# fpga-power.net
KiCad netlist of a schematic drawn in Altium Designer
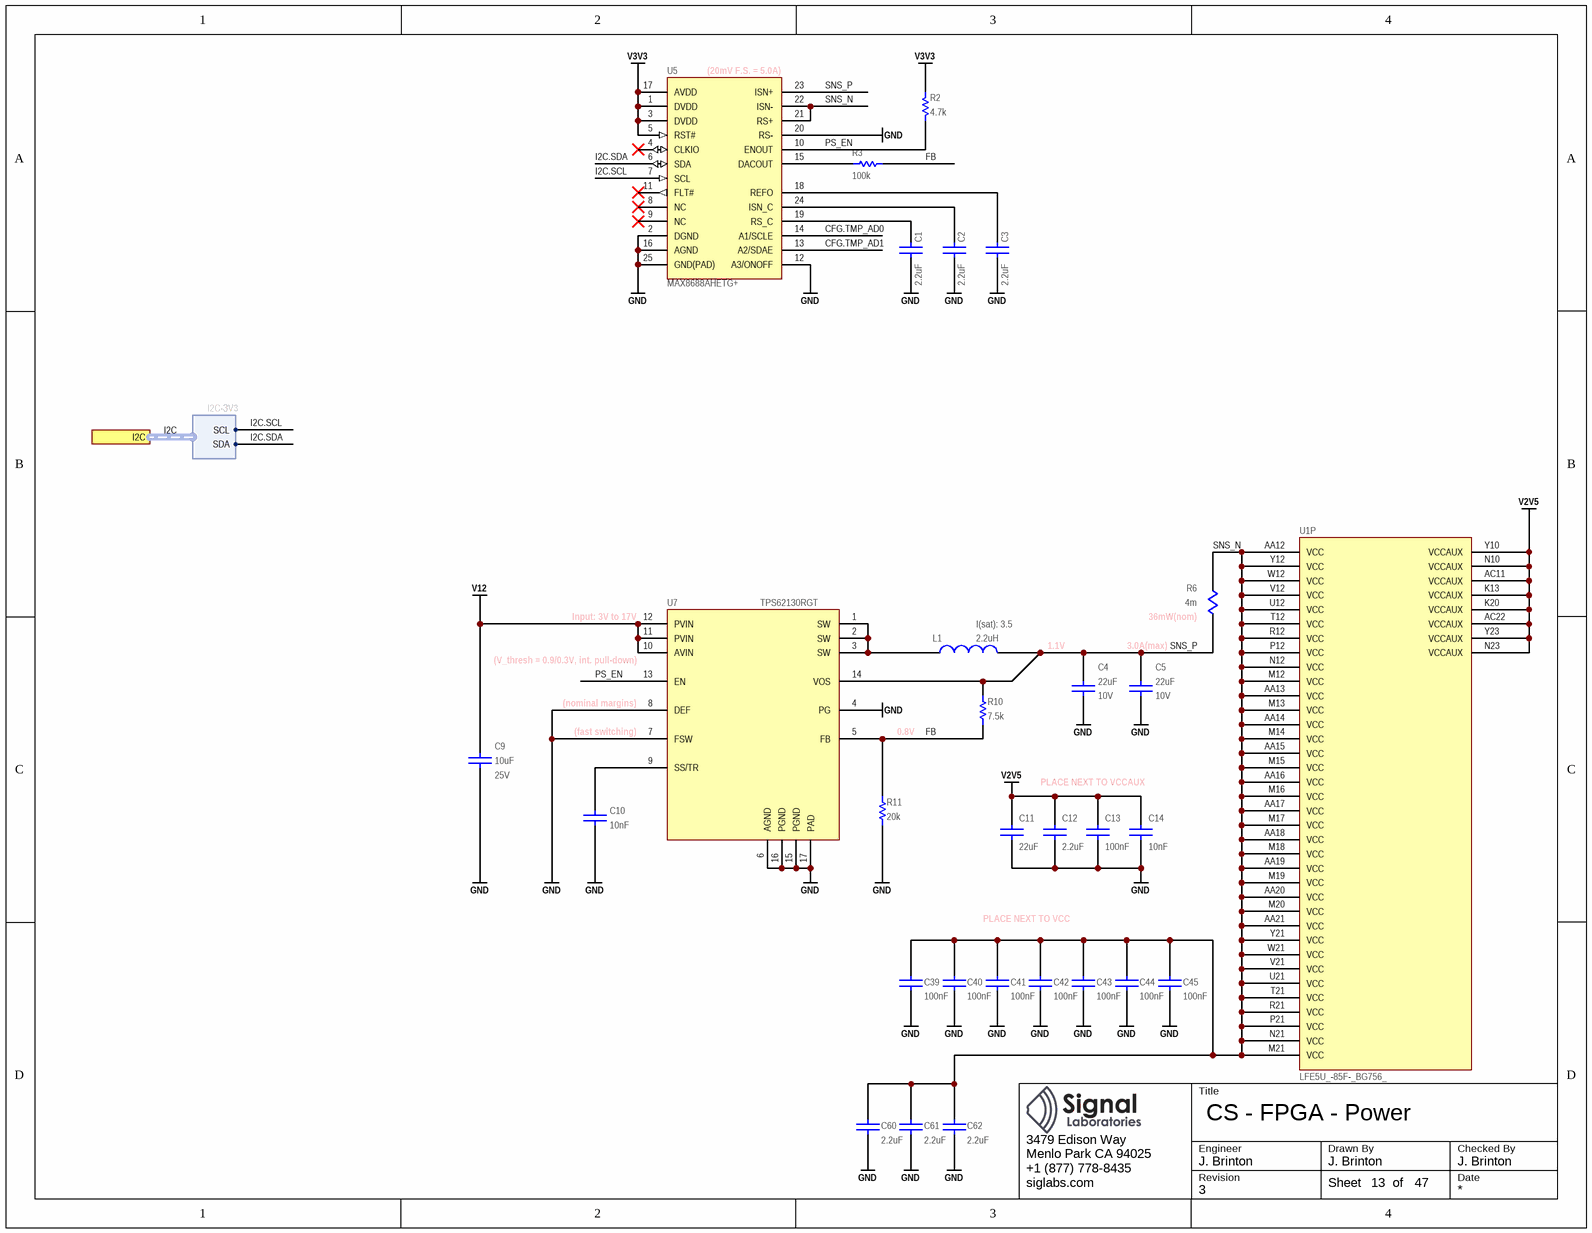
[diagram p0: fpga-power.SchDoc]

(export (version "E")
  (design (tool "Eeschema 10.0.6"))
  (components
    (comp (ref "C1")
      (value "2.2uF")
      (footprint "CAPC160X80X90L20N")
      (description "Ceramic Capacitor 2.2uF ±20% 10V X7R 0603")
      (fields (field (name "MANUFACTURER") "TDK") (field (name "TOLERANCE") "±20%"))
      (libsource (lib "generic") (part "CAP"))
    )
    (comp (ref "C2")
      (value "2.2uF")
      (footprint "CAPC160X80X90L20N")
      (description "Ceramic Capacitor 2.2uF ±20% 10V X7R 0603")
      (fields (field (name "MANUFACTURER") "TDK") (field (name "TOLERANCE") "±20%"))
      (libsource (lib "generic") (part "CAP"))
    )
    (comp (ref "C3")
      (value "2.2uF")
      (footprint "CAPC160X80X90L20N")
      (description "Ceramic Capacitor 2.2uF ±20% 10V X7R 0603")
      (fields (field (name "MANUFACTURER") "TDK") (field (name "TOLERANCE") "±20%"))
      (libsource (lib "generic") (part "CAP"))
    )
    (comp (ref "C4")
      (value "22uF")
      (footprint "CAPC200X125X145L45N")
      (description "Ceramic Capacitor 22uF ±20% 10V X7S 0805")
      (fields
        (field (name "MANUFACTURER") "TDK")
        (field (name "TOLERANCE") "±20%")
        (field (name "VOLTAGE") "10V")
      )
      (libsource (lib "generic") (part "CAP"))
    )
    (comp (ref "C5")
      (value "22uF")
      (footprint "CAPC200X125X145L45N")
      (description "Ceramic Capacitor 22uF ±20% 10V X7S 0805")
      (fields
        (field (name "MANUFACTURER") "TDK")
        (field (name "TOLERANCE") "±20%")
        (field (name "VOLTAGE") "10V")
      )
      (libsource (lib "generic") (part "CAP"))
    )
    (comp (ref "C9")
      (value "10uF")
      (footprint "CAPC200X125X145L45N")
      (description "Ceramic Capacitor 10uF ±10% 25V X6S 0805")
      (fields
        (field (name "MANUFACTURER") "Murata")
        (field (name "TOLERANCE") "±10%")
        (field (name "VOLTAGE") "25V")
      )
      (libsource (lib "") (part "CAP_1"))
    )
    (comp (ref "C10")
      (value "10nF")
      (footprint "CAPC100X50X55L25N")
      (description "Ceramic Capacitor 10nF ±10% 50V X7R 0402")
      (fields (field (name "MANUFACTURER") "Murata") (field (name "TOLERANCE") "±10%"))
      (libsource (lib "") (part "CAP_1"))
    )
    (comp (ref "C11")
      (value "22uF")
      (footprint "CAPC200X125X145L45N")
      (description "Ceramic Capacitor 22uF ±20% 10V X7S 0805")
      (fields (field (name "MANUFACTURER") "TDK") (field (name "TOLERANCE") "±20%"))
      (libsource (lib "generic") (part "CAP"))
    )
    (comp (ref "C12")
      (value "2.2uF")
      (footprint "CAPC160X80X90L20N")
      (description "Ceramic Capacitor 2.2uF ±20% 10V X7R 0603")
      (fields (field (name "MANUFACTURER") "TDK") (field (name "TOLERANCE") "±20%"))
      (libsource (lib "generic") (part "CAP"))
    )
    (comp (ref "C13")
      (value "100nF")
      (footprint "CAPC100X50X55L25N")
      (description "Ceramic Capacitor 100nF ±10% 50V X7R 0402")
      (fields (field (name "MANUFACTURER") "Murata") (field (name "TOLERANCE") "±10%"))
      (libsource (lib "generic") (part "CAP"))
    )
    (comp (ref "C14")
      (value "10nF")
      (footprint "CAPC100X50X55L25N")
      (description "Ceramic Capacitor 10nF ±10% 50V X7R 0402")
      (fields (field (name "MANUFACTURER") "Murata") (field (name "TOLERANCE") "±10%"))
      (libsource (lib "") (part "CAP_1"))
    )
    (comp (ref "C39")
      (value "100nF")
      (footprint "CAPC100X50X55L25N")
      (description "Ceramic Capacitor 100nF ±10% 50V X7R 0402")
      (fields (field (name "MANUFACTURER") "Murata") (field (name "TOLERANCE") "±10%"))
      (libsource (lib "generic") (part "CAP"))
    )
    (comp (ref "C40")
      (value "100nF")
      (footprint "CAPC100X50X55L25N")
      (description "Ceramic Capacitor 100nF ±10% 50V X7R 0402")
      (fields (field (name "MANUFACTURER") "Murata") (field (name "TOLERANCE") "±10%"))
      (libsource (lib "generic") (part "CAP"))
    )
    (comp (ref "C41")
      (value "100nF")
      (footprint "CAPC100X50X55L25N")
      (description "Ceramic Capacitor 100nF ±10% 50V X7R 0402")
      (fields (field (name "MANUFACTURER") "Murata") (field (name "TOLERANCE") "±10%"))
      (libsource (lib "generic") (part "CAP"))
    )
    (comp (ref "C42")
      (value "100nF")
      (footprint "CAPC100X50X55L25N")
      (description "Ceramic Capacitor 100nF ±10% 50V X7R 0402")
      (fields (field (name "MANUFACTURER") "Murata") (field (name "TOLERANCE") "±10%"))
      (libsource (lib "generic") (part "CAP"))
    )
    (comp (ref "C43")
      (value "100nF")
      (footprint "CAPC100X50X55L25N")
      (description "Ceramic Capacitor 100nF ±10% 50V X7R 0402")
      (fields (field (name "MANUFACTURER") "Murata") (field (name "TOLERANCE") "±10%"))
      (libsource (lib "generic") (part "CAP"))
    )
    (comp (ref "C44")
      (value "100nF")
      (footprint "CAPC100X50X55L25N")
      (description "Ceramic Capacitor 100nF ±10% 50V X7R 0402")
      (fields (field (name "MANUFACTURER") "Murata") (field (name "TOLERANCE") "±10%"))
      (libsource (lib "generic") (part "CAP"))
    )
    (comp (ref "C45")
      (value "100nF")
      (footprint "CAPC100X50X55L25N")
      (description "Ceramic Capacitor 100nF ±10% 50V X7R 0402")
      (fields (field (name "MANUFACTURER") "Murata") (field (name "TOLERANCE") "±10%"))
      (libsource (lib "generic") (part "CAP"))
    )
    (comp (ref "C60")
      (value "2.2uF")
      (footprint "CAPC160X80X90L20N")
      (description "Ceramic Capacitor 2.2uF ±20% 10V X7R 0603")
      (fields (field (name "MANUFACTURER") "TDK") (field (name "TOLERANCE") "±20%"))
      (libsource (lib "generic") (part "CAP"))
    )
    (comp (ref "C61")
      (value "2.2uF")
      (footprint "CAPC160X80X90L20N")
      (description "Ceramic Capacitor 2.2uF ±20% 10V X7R 0603")
      (fields (field (name "MANUFACTURER") "TDK") (field (name "TOLERANCE") "±20%"))
      (libsource (lib "generic") (part "CAP"))
    )
    (comp (ref "C62")
      (value "2.2uF")
      (footprint "CAPC160X80X90L20N")
      (description "Ceramic Capacitor 2.2uF ±20% 10V X7R 0603")
      (fields (field (name "MANUFACTURER") "TDK") (field (name "TOLERANCE") "±20%"))
      (libsource (lib "generic") (part "CAP"))
    )
    (comp (ref "L1")
      (value "2.2uH")
      (footprint "coilcraft:XFL4020")
      (description "Wirewound Inductor 2.2uH +/-20% 3.5A SMD")
      (fields
        (field (name "MANUFACTURER") "Coilcraft")
        (field (name "I(SAT)") "3.5")
        (field (name "Comment") "XFL4020-222ME")
      )
      (libsource (lib "CamBoard_Pico_70.19K") (part "COIL"))
    )
    (comp (ref "R2")
      (value "4.7k")
      (footprint "RESC1005X40N")
      (description "Thick Film Resistor 4.7k ±1% 0.1W 75V 0402")
      (fields (field (name "TOLERANCE") "±1%") (field (name "MANUFACTURER") "Panasonic"))
      (libsource (lib "generic") (part "RES"))
    )
    (comp (ref "R3")
      (value "100k")
      (footprint "RESC1005X40N")
      (description "Thick Film Resistor 100k ±1% 0.1W 50V 0402")
      (fields (field (name "MANUFACTURER") "Panasonic") (field (name "TOLERANCE") "±1%"))
      (libsource (lib "generic") (part "RES"))
    )
    (comp (ref "R6")
      (value "4m")
      (footprint "RESC3216X80L110N")
      (description "Current Sense Resistor 4mOhm +/-1% SMD 1206")
      (fields (field (name "MANUFACTURER") "Riedon") (field (name "Comment") "CSR1206-0R004F1"))
      (libsource (lib "Kron Library Rev 3") (part "CSR1206-0R001F1"))
    )
    (comp (ref "R10")
      (value "7.5k")
      (footprint "RESC2012X70N")
      (description "Thin Film Resistor 7.5k ±0.1% 0.125W 100V 0805")
      (fields (field (name "TOLERANCE") "±0.1%") (field (name "MANUFACTURER") "Panasonic"))
      (libsource (lib "generic") (part "RES"))
    )
    (comp (ref "R11")
      (value "20k")
      (footprint "RESC2012X70N")
      (description "Thin Film Resistor 20k ±0.1% 0.125W 100V 0805")
      (fields (field (name "TOLERANCE") "±0.1%") (field (name "MANUFACTURER") "Panasonic"))
      (libsource (lib "generic") (part "RES"))
    )
    (comp (ref "U1")
      (value "LFE5U_-85F-_BG756_")
      (footprint "lattice:caBGA756")
      (description "ECP5 FPGA, 85k LUT, 756-caBGA")
      (fields (field (name "MANUFACTURER") "Lattice Semiconductor"))
      (libsource (lib "lattice") (part "LFE5U_-85F-_BG756_"))
    )
    (comp (ref "U5")
      (value "MAX8688AHETG+")
      (footprint "generic:QFN25P50_400X400X80L40X24T260N")
      (description "Digital Power-Supply Controller/Monitor")
      (fields (field (name "MANUFACTURER") "Maxim Integrated"))
      (libsource (lib "maxim") (part "MAX8688AHETG+"))
    )
    (comp (ref "U7")
      (value "TPS62130RGT")
      (footprint "S-PQFP-8N_NOVIA")
      (description "3-17V 3A Step-Down Converter VQFN")
      (fields (field (name "MANUFACTURER") "Texas Instruments"))
      (libsource (lib "ti") (part "TPS62130RGT"))
    )
  )
  (nets
    (net (code "2") (name "/CFG.TMP_AD0") (class "Default")
      (node (ref "U5") (pin "14") (pinfunction "A1/SCLE_14") (pintype "passive"))
    )
    (net (code "3") (name "/CFG.TMP_AD1") (class "Default")
      (node (ref "U5") (pin "13") (pinfunction "A2/SDAE_13") (pintype "passive"))
    )
    (net (code "4") (name "/FB") (class "Default")
      (node (ref "R10") (pin "1") (pinfunction "1_1") (pintype "passive"))
      (node (ref "R11") (pin "2") (pinfunction "2_2") (pintype "passive"))
      (node (ref "R3") (pin "2") (pinfunction "2_2") (pintype "passive"))
      (node (ref "U7") (pin "5") (pinfunction "FB_5") (pintype "passive"))
    )
    (net (code "5") (name "/I2C.SCL") (class "Default")
      (node (ref "U5") (pin "7") (pinfunction "SCL_7") (pintype "input"))
    )
    (net (code "6") (name "/I2C.SDA") (class "Default")
      (node (ref "U5") (pin "6") (pinfunction "SDA_6") (pintype "bidirectional"))
    )
    (net (code "8") (name "/PS_EN") (class "Default")
      (node (ref "R2") (pin "1") (pinfunction "1_1") (pintype "passive"))
      (node (ref "U5") (pin "10") (pinfunction "ENOUT_10") (pintype "passive"))
      (node (ref "U7") (pin "13") (pinfunction "EN_13") (pintype "passive"))
    )
    (net (code "9") (name "/SNS_N") (class "Default")
      (node (ref "C39") (pin "2") (pinfunction "2_2") (pintype "passive"))
      (node (ref "C40") (pin "2") (pinfunction "2_2") (pintype "passive"))
      (node (ref "C41") (pin "2") (pinfunction "2_2") (pintype "passive"))
      (node (ref "C42") (pin "2") (pinfunction "2_2") (pintype "passive"))
      (node (ref "C43") (pin "2") (pinfunction "2_2") (pintype "passive"))
      (node (ref "C44") (pin "2") (pinfunction "2_2") (pintype "passive"))
      (node (ref "C45") (pin "2") (pinfunction "2_2") (pintype "passive"))
      (node (ref "C60") (pin "2") (pinfunction "2_2") (pintype "passive"))
      (node (ref "C61") (pin "2") (pinfunction "2_2") (pintype "passive"))
      (node (ref "C62") (pin "2") (pinfunction "2_2") (pintype "passive"))
      (node (ref "R6") (pin "2") (pintype "passive"))
      (node (ref "U1") (pin "AA12") (pinfunction "VCC_AA12") (pintype "power_in"))
      (node (ref "U1") (pin "AA13") (pinfunction "VCC_AA13") (pintype "power_in"))
      (node (ref "U1") (pin "AA14") (pinfunction "VCC_AA14") (pintype "power_in"))
      (node (ref "U1") (pin "AA15") (pinfunction "VCC_AA15") (pintype "power_in"))
      (node (ref "U1") (pin "AA16") (pinfunction "VCC_AA16") (pintype "power_in"))
      (node (ref "U1") (pin "AA17") (pinfunction "VCC_AA17") (pintype "power_in"))
      (node (ref "U1") (pin "AA18") (pinfunction "VCC_AA18") (pintype "power_in"))
      (node (ref "U1") (pin "AA19") (pinfunction "VCC_AA19") (pintype "power_in"))
      (node (ref "U1") (pin "AA20") (pinfunction "VCC_AA20") (pintype "power_in"))
      (node (ref "U1") (pin "AA21") (pinfunction "VCC_AA21") (pintype "power_in"))
      (node (ref "U1") (pin "M12") (pinfunction "VCC_M12") (pintype "power_in"))
      (node (ref "U1") (pin "M13") (pinfunction "VCC_M13") (pintype "power_in"))
      (node (ref "U1") (pin "M14") (pinfunction "VCC_M14") (pintype "power_in"))
      (node (ref "U1") (pin "M15") (pinfunction "VCC_M15") (pintype "power_in"))
      (node (ref "U1") (pin "M16") (pinfunction "VCC_M16") (pintype "power_in"))
      (node (ref "U1") (pin "M17") (pinfunction "VCC_M17") (pintype "power_in"))
      (node (ref "U1") (pin "M18") (pinfunction "VCC_M18") (pintype "power_in"))
      (node (ref "U1") (pin "M19") (pinfunction "VCC_M19") (pintype "power_in"))
      (node (ref "U1") (pin "M20") (pinfunction "VCC_M20") (pintype "power_in"))
      (node (ref "U1") (pin "M21") (pinfunction "VCC_M21") (pintype "power_in"))
      (node (ref "U1") (pin "N12") (pinfunction "VCC_N12") (pintype "power_in"))
      (node (ref "U1") (pin "N21") (pinfunction "VCC_N21") (pintype "power_in"))
      (node (ref "U1") (pin "P12") (pinfunction "VCC_P12") (pintype "power_in"))
      (node (ref "U1") (pin "P21") (pinfunction "VCC_P21") (pintype "power_in"))
      (node (ref "U1") (pin "R12") (pinfunction "VCC_R12") (pintype "power_in"))
      (node (ref "U1") (pin "R21") (pinfunction "VCC_R21") (pintype "power_in"))
      (node (ref "U1") (pin "T12") (pinfunction "VCC_T12") (pintype "power_in"))
      (node (ref "U1") (pin "T21") (pinfunction "VCC_T21") (pintype "power_in"))
      (node (ref "U1") (pin "U12") (pinfunction "VCC_U12") (pintype "power_in"))
      (node (ref "U1") (pin "U21") (pinfunction "VCC_U21") (pintype "power_in"))
      (node (ref "U1") (pin "V12") (pinfunction "VCC_V12") (pintype "power_in"))
      (node (ref "U1") (pin "V21") (pinfunction "VCC_V21") (pintype "power_in"))
      (node (ref "U1") (pin "W12") (pinfunction "VCC_W12") (pintype "power_in"))
      (node (ref "U1") (pin "W21") (pinfunction "VCC_W21") (pintype "power_in"))
      (node (ref "U1") (pin "Y12") (pinfunction "VCC_Y12") (pintype "power_in"))
      (node (ref "U1") (pin "Y21") (pinfunction "VCC_Y21") (pintype "power_in"))
      (node (ref "U5") (pin "21") (pinfunction "RS+_21") (pintype "passive"))
      (node (ref "U5") (pin "22") (pinfunction "ISN-_22") (pintype "passive"))
    )
    (net (code "10") (name "/SNS_P") (class "Default")
      (node (ref "C4") (pin "2") (pinfunction "2_2") (pintype "passive"))
      (node (ref "C5") (pin "2") (pinfunction "2_2") (pintype "passive"))
      (node (ref "L1") (pin "2") (pinfunction "2_2") (pintype "passive"))
      (node (ref "R10") (pin "2") (pinfunction "2_2") (pintype "passive"))
      (node (ref "R6") (pin "1") (pintype "passive"))
      (node (ref "U5") (pin "23") (pinfunction "ISN+_23") (pintype "passive"))
      (node (ref "U7") (pin "14") (pinfunction "VOS_14") (pintype "passive"))
    )
    (net (code "11") (name "GND") (class "Default")
      (node (ref "C1") (pin "1") (pinfunction "1_1") (pintype "passive"))
      (node (ref "C10") (pin "2") (pinfunction "2_2") (pintype "passive"))
      (node (ref "C11") (pin "1") (pinfunction "1_1") (pintype "passive"))
      (node (ref "C12") (pin "1") (pinfunction "1_1") (pintype "passive"))
      (node (ref "C13") (pin "1") (pinfunction "1_1") (pintype "passive"))
      (node (ref "C14") (pin "2") (pinfunction "2_2") (pintype "passive"))
      (node (ref "C2") (pin "1") (pinfunction "1_1") (pintype "passive"))
      (node (ref "C3") (pin "1") (pinfunction "1_1") (pintype "passive"))
      (node (ref "C39") (pin "1") (pinfunction "1_1") (pintype "passive"))
      (node (ref "C4") (pin "1") (pinfunction "1_1") (pintype "passive"))
      (node (ref "C40") (pin "1") (pinfunction "1_1") (pintype "passive"))
      (node (ref "C41") (pin "1") (pinfunction "1_1") (pintype "passive"))
      (node (ref "C42") (pin "1") (pinfunction "1_1") (pintype "passive"))
      (node (ref "C43") (pin "1") (pinfunction "1_1") (pintype "passive"))
      (node (ref "C44") (pin "1") (pinfunction "1_1") (pintype "passive"))
      (node (ref "C45") (pin "1") (pinfunction "1_1") (pintype "passive"))
      (node (ref "C5") (pin "1") (pinfunction "1_1") (pintype "passive"))
      (node (ref "C60") (pin "1") (pinfunction "1_1") (pintype "passive"))
      (node (ref "C61") (pin "1") (pinfunction "1_1") (pintype "passive"))
      (node (ref "C62") (pin "1") (pinfunction "1_1") (pintype "passive"))
      (node (ref "C9") (pin "1") (pinfunction "1_1") (pintype "passive"))
      (node (ref "R11") (pin "1") (pinfunction "1_1") (pintype "passive"))
      (node (ref "U5") (pin "12") (pinfunction "A3/ONOFF_12") (pintype "passive"))
      (node (ref "U5") (pin "16") (pinfunction "AGND_16") (pintype "power_in"))
      (node (ref "U5") (pin "2") (pinfunction "DGND_2") (pintype "power_in"))
      (node (ref "U5") (pin "20") (pinfunction "RS-_20") (pintype "passive"))
      (node (ref "U5") (pin "25") (pinfunction "GND(PAD)_25") (pintype "power_in"))
      (node (ref "U7") (pin "15") (pinfunction "PGND_15") (pintype "passive"))
      (node (ref "U7") (pin "16") (pinfunction "PGND_16") (pintype "passive"))
      (node (ref "U7") (pin "17") (pinfunction "PAD_17") (pintype "passive"))
      (node (ref "U7") (pin "4") (pinfunction "PG_4") (pintype "passive"))
      (node (ref "U7") (pin "6") (pinfunction "AGND_6") (pintype "passive"))
      (node (ref "U7") (pin "7") (pinfunction "FSW_7") (pintype "passive"))
      (node (ref "U7") (pin "8") (pinfunction "DEF_8") (pintype "passive"))
    )
    (net (code "12") (name "Net-(L1-Pad1)") (class "Default")
      (node (ref "L1") (pin "1") (pinfunction "1_1") (pintype "passive"))
      (node (ref "U7") (pin "1") (pinfunction "SW_1") (pintype "passive"))
      (node (ref "U7") (pin "2") (pinfunction "SW_2") (pintype "passive"))
      (node (ref "U7") (pin "3") (pinfunction "SW_3") (pintype "passive"))
    )
    (net (code "13") (name "Net-(U5-DACOUT)") (class "Default")
      (node (ref "R3") (pin "1") (pinfunction "1_1") (pintype "passive"))
      (node (ref "U5") (pin "15") (pinfunction "DACOUT_15") (pintype "passive"))
    )
    (net (code "14") (name "Net-(U5-ISN_C)") (class "Default")
      (node (ref "C2") (pin "2") (pinfunction "2_2") (pintype "passive"))
      (node (ref "U5") (pin "24") (pinfunction "ISN_C_24") (pintype "passive"))
    )
    (net (code "15") (name "Net-(U5-REFO)") (class "Default")
      (node (ref "C3") (pin "2") (pinfunction "2_2") (pintype "passive"))
      (node (ref "U5") (pin "18") (pinfunction "REFO_18") (pintype "passive"))
    )
    (net (code "16") (name "Net-(U5-RS_C)") (class "Default")
      (node (ref "C1") (pin "2") (pinfunction "2_2") (pintype "passive"))
      (node (ref "U5") (pin "19") (pinfunction "RS_C_19") (pintype "passive"))
    )
    (net (code "17") (name "Net-(U7-SS{slash}TR)") (class "Default")
      (node (ref "C10") (pin "1") (pinfunction "1_1") (pintype "passive"))
      (node (ref "U7") (pin "9") (pinfunction "SS/TR_9") (pintype "passive"))
    )
    (net (code "18") (name "V2V5") (class "Default")
      (node (ref "C11") (pin "2") (pinfunction "2_2") (pintype "passive"))
      (node (ref "C12") (pin "2") (pinfunction "2_2") (pintype "passive"))
      (node (ref "C13") (pin "2") (pinfunction "2_2") (pintype "passive"))
      (node (ref "C14") (pin "1") (pinfunction "1_1") (pintype "passive"))
      (node (ref "U1") (pin "AC11") (pinfunction "VCCAUX_AC11") (pintype "power_in"))
      (node (ref "U1") (pin "AC22") (pinfunction "VCCAUX_AC22") (pintype "power_in"))
      (node (ref "U1") (pin "K13") (pinfunction "VCCAUX_K13") (pintype "power_in"))
      (node (ref "U1") (pin "K20") (pinfunction "VCCAUX_K20") (pintype "power_in"))
      (node (ref "U1") (pin "N10") (pinfunction "VCCAUX_N10") (pintype "power_in"))
      (node (ref "U1") (pin "N23") (pinfunction "VCCAUX_N23") (pintype "power_in"))
      (node (ref "U1") (pin "Y10") (pinfunction "VCCAUX_Y10") (pintype "power_in"))
      (node (ref "U1") (pin "Y23") (pinfunction "VCCAUX_Y23") (pintype "power_in"))
    )
    (net (code "19") (name "V3V3") (class "Default")
      (node (ref "R2") (pin "2") (pinfunction "2_2") (pintype "passive"))
      (node (ref "U5") (pin "1") (pinfunction "DVDD_1") (pintype "power_in"))
      (node (ref "U5") (pin "17") (pinfunction "AVDD_17") (pintype "power_in"))
      (node (ref "U5") (pin "3") (pinfunction "DVDD_3") (pintype "power_in"))
      (node (ref "U5") (pin "5") (pinfunction "RST#_5") (pintype "input"))
    )
    (net (code "20") (name "V12") (class "Default")
      (node (ref "C9") (pin "2") (pinfunction "2_2") (pintype "passive"))
      (node (ref "U7") (pin "10") (pinfunction "AVIN_10") (pintype "passive"))
      (node (ref "U7") (pin "11") (pinfunction "PVIN_11") (pintype "passive"))
      (node (ref "U7") (pin "12") (pinfunction "PVIN_12") (pintype "passive"))
    )
    (net (code "21") (name "unconnected-(U5-CLKIO-Pad4)") (class "Default")
      (node (ref "U5") (pin "4") (pinfunction "CLKIO_4") (pintype "bidirectional+no_connect"))
    )
    (net (code "22") (name "unconnected-(U5-FLT#-Pad11)") (class "Default")
      (node (ref "U5") (pin "11") (pinfunction "FLT#_11") (pintype "output+no_connect"))
    )
    (net (code "23") (name "unconnected-(U5-NC-Pad8)") (class "Default")
      (node (ref "U5") (pin "8") (pinfunction "NC_8") (pintype "passive+no_connect"))
    )
    (net (code "24") (name "unconnected-(U5-NC-Pad9)") (class "Default")
      (node (ref "U5") (pin "9") (pinfunction "NC_9") (pintype "passive+no_connect"))
    )
  )
)
